# Regensensor.net
KiCad netlist of a schematic drawn in EAGLE
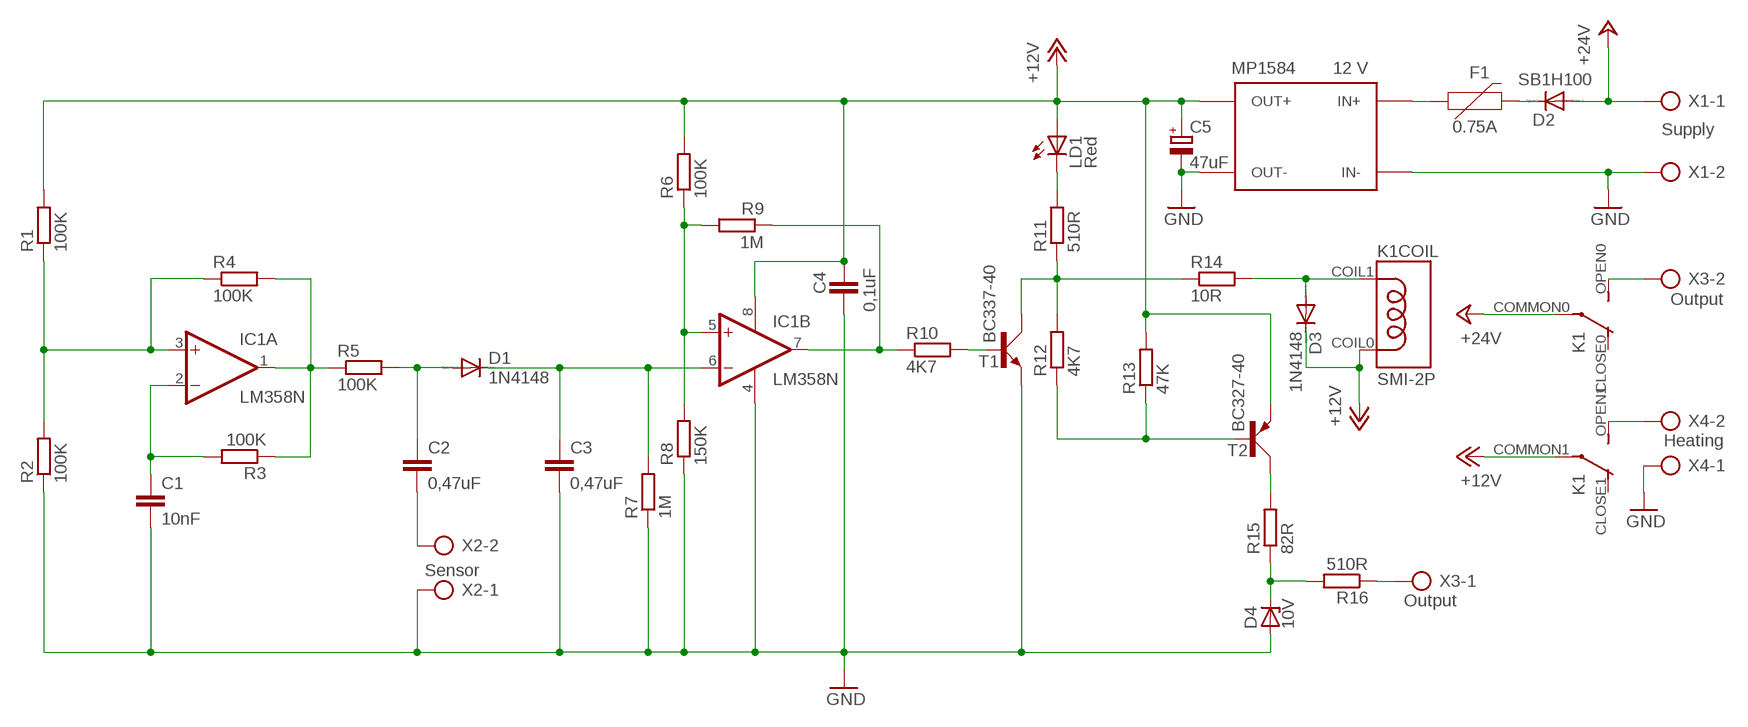
[diagram p0: schematic, sheet 1]

(export (version "E")
  (design (tool "Eeschema 10.0.6"))
  (components
    (comp (ref "C1")
      (value "10nF")
      (footprint "eagle-import:C050-055X075")
      (libsource (lib "eagle-import") (part "C-EU050-055X075"))
    )
    (comp (ref "C2")
      (value "0,47uF")
      (footprint "eagle-import:C050-035X075")
      (libsource (lib "eagle-import") (part "C-EU050-035X075"))
    )
    (comp (ref "C3")
      (value "0,47uF")
      (footprint "eagle-import:C050-035X075")
      (libsource (lib "eagle-import") (part "C-EU050-035X075"))
    )
    (comp (ref "C4")
      (value "0,1uF")
      (footprint "eagle-import:C025-030X050")
      (libsource (lib "eagle-import") (part "C-EU025-030X050"))
    )
    (comp (ref "C5")
      (value "47uF")
      (footprint "eagle-import:E2,5-7")
      (libsource (lib "eagle-import") (part "CPOL-EUE2.5-7"))
    )
    (comp (ref "D1")
      (value "1N4148")
      (footprint "eagle-import:DO35-2V")
      (libsource (lib "eagle-import") (part "1N4148DO35-2V"))
    )
    (comp (ref "D2")
      (value "SB1H100")
      (footprint "eagle-import:DO41-7.6")
      (libsource (lib "eagle-import") (part "DIODE-DO41-7.6"))
    )
    (comp (ref "D3")
      (value "1N4148")
      (footprint "eagle-import:DO35-7")
      (libsource (lib "eagle-import") (part "1N4148DO35-7"))
    )
    (comp (ref "D4")
      (value "10V")
      (footprint "eagle-import:ZDIO-2.5")
      (libsource (lib "eagle-import") (part "ZENER-DIODEZD-2.5"))
    )
    (comp (ref "F1")
      (value "0.75A")
      (footprint "eagle-import:RGEF250")
      (libsource (lib "eagle-import") (part "PPTCRGEF250"))
    )
    (comp (ref "IC1")
      (value "LM358N")
      (footprint "eagle-import:DIL08")
      (libsource (lib "eagle-import") (part "LM358N"))
    )
    (comp (ref "K1")
      (value "SMI-2P")
      (footprint "eagle-import:SMI")
      (libsource (lib "eagle-import") (part "SMI-2P"))
    )
    (comp (ref "LD1")
      (value "Red")
      (footprint "eagle-import:LED5MM")
      (libsource (lib "eagle-import") (part "LED5MM"))
    )
    (comp (ref "MP1584")
      (value "12 V")
      (footprint "eagle-import:MP1584")
      (libsource (lib "eagle-import") (part "DC-DC-STEP-DOWNMP1584"))
    )
    (comp (ref "R1")
      (value "100K")
      (footprint "eagle-import:0204V")
      (libsource (lib "eagle-import") (part "R-EU_0204/2V"))
    )
    (comp (ref "R2")
      (value "100K")
      (footprint "eagle-import:0204V")
      (libsource (lib "eagle-import") (part "R-EU_0204/2V"))
    )
    (comp (ref "R3")
      (value "100K")
      (footprint "eagle-import:0204V")
      (libsource (lib "eagle-import") (part "R-EU_0204/2V"))
    )
    (comp (ref "R4")
      (value "100K")
      (footprint "eagle-import:0204_5")
      (libsource (lib "eagle-import") (part "R-EU_0204/5"))
    )
    (comp (ref "R5")
      (value "100K")
      (footprint "eagle-import:0204V")
      (libsource (lib "eagle-import") (part "R-EU_0204/2V"))
    )
    (comp (ref "R6")
      (value "100K")
      (footprint "eagle-import:0204_5")
      (libsource (lib "eagle-import") (part "R-EU_0204/5"))
    )
    (comp (ref "R7")
      (value "1M")
      (footprint "eagle-import:0204V")
      (libsource (lib "eagle-import") (part "R-EU_0204/2V"))
    )
    (comp (ref "R8")
      (value "150K")
      (footprint "eagle-import:0204_5")
      (libsource (lib "eagle-import") (part "R-EU_0204/5"))
    )
    (comp (ref "R9")
      (value "1M")
      (footprint "eagle-import:0204_5")
      (libsource (lib "eagle-import") (part "R-EU_0204/5"))
    )
    (comp (ref "R10")
      (value "4K7")
      (footprint "eagle-import:0204_5")
      (libsource (lib "eagle-import") (part "R-EU_0204/5"))
    )
    (comp (ref "R11")
      (value "510R")
      (footprint "eagle-import:0204V")
      (libsource (lib "eagle-import") (part "R-EU_0204/2V"))
    )
    (comp (ref "R12")
      (value "4K7")
      (footprint "eagle-import:0204V")
      (libsource (lib "eagle-import") (part "R-EU_0204/2V"))
    )
    (comp (ref "R13")
      (value "47K")
      (footprint "eagle-import:0204V")
      (libsource (lib "eagle-import") (part "R-EU_0204/2V"))
    )
    (comp (ref "R14")
      (value "10R")
      (footprint "eagle-import:0204V")
      (libsource (lib "eagle-import") (part "R-EU_0204/2V"))
    )
    (comp (ref "R15")
      (value "82R")
      (footprint "eagle-import:0204V")
      (libsource (lib "eagle-import") (part "R-EU_0204/2V"))
    )
    (comp (ref "R16")
      (value "510R")
      (footprint "eagle-import:0204V")
      (libsource (lib "eagle-import") (part "R-EU_0204/2V"))
    )
    (comp (ref "T1")
      (value "BC337-40")
      (footprint "eagle-import:TO92-LINE")
      (libsource (lib "eagle-import") (part "BC337LINE"))
    )
    (comp (ref "T2")
      (value "BC327-40")
      (footprint "eagle-import:TO92-LINE")
      (libsource (lib "eagle-import") (part "BC327LINE"))
    )
    (comp (ref "X1")
      (value "Supply")
      (footprint "eagle-import:MKDSB-3_2-2")
      (libsource (lib "eagle-import") (part "MKDS-3/25,08"))
    )
    (comp (ref "X2")
      (value "Sensor")
      (footprint "eagle-import:MKDSB-3_2-2")
      (libsource (lib "eagle-import") (part "MKDS-3/25,08"))
    )
    (comp (ref "X3")
      (value "Output")
      (footprint "eagle-import:MKDSB-3_2-2")
      (libsource (lib "eagle-import") (part "MKDS-3/25,08"))
    )
    (comp (ref "X4")
      (value "Heating")
      (footprint "eagle-import:MKDSB-3_2-2")
      (libsource (lib "eagle-import") (part "MKDS-3/25,08"))
    )
  )
  (nets
    (net (code "1") (name "+12V") (class "Default")
      (node (ref "C4") (pin "1") (pinfunction "1_1") (pintype "passive"))
      (node (ref "C5") (pin "+") (pinfunction "+_+") (pintype "passive"))
      (node (ref "D3") (pin "C") (pinfunction "C_C") (pintype "passive"))
      (node (ref "IC1") (pin "8") (pinfunction "V+_8") (pintype "power_in"))
      (node (ref "K1") (pin "COIL0") (pinfunction "0_COIL0") (pintype "passive"))
      (node (ref "K1") (pin "COMMON1") (pinfunction "COMMON_COMMON1") (pintype "passive"))
      (node (ref "LD1") (pin "A") (pinfunction "A_A") (pintype "passive"))
      (node (ref "MP1584") (pin "OUT+0") (pinfunction "OUT+_OUT+0") (pintype "power_in"))
      (node (ref "MP1584") (pin "OUT+1") (pinfunction "OUT+_OUT+1") (pintype "power_in"))
      (node (ref "R1") (pin "2") (pinfunction "2_2") (pintype "passive"))
      (node (ref "R13") (pin "2") (pinfunction "2_2") (pintype "passive"))
      (node (ref "R6") (pin "2") (pinfunction "2_2") (pintype "passive"))
      (node (ref "T2") (pin "1") (pinfunction "E_1") (pintype "passive"))
    )
    (net (code "2") (name "+24V") (class "Default")
      (node (ref "D2") (pin "A") (pinfunction "A_A") (pintype "passive"))
      (node (ref "K1") (pin "COMMON0") (pinfunction "COMMON_COMMON0") (pintype "passive"))
      (node (ref "X1") (pin "1") (pinfunction "KL_1") (pintype "passive"))
    )
    (net (code "3") (name "GND") (class "Default")
      (node (ref "C1") (pin "2") (pinfunction "2_2") (pintype "passive"))
      (node (ref "C3") (pin "2") (pinfunction "2_2") (pintype "passive"))
      (node (ref "C4") (pin "2") (pinfunction "2_2") (pintype "passive"))
      (node (ref "C5") (pin "-") (pinfunction "-_-") (pintype "passive"))
      (node (ref "D4") (pin "A") (pinfunction "A_A") (pintype "passive"))
      (node (ref "IC1") (pin "4") (pinfunction "V-_4") (pintype "power_in"))
      (node (ref "MP1584") (pin "IN-0") (pinfunction "IN-_IN-0") (pintype "power_in"))
      (node (ref "MP1584") (pin "IN-1") (pinfunction "IN-_IN-1") (pintype "power_in"))
      (node (ref "MP1584") (pin "OUT-0") (pinfunction "OUT-_OUT-0") (pintype "power_in"))
      (node (ref "MP1584") (pin "OUT-1") (pinfunction "OUT-_OUT-1") (pintype "power_in"))
      (node (ref "R2") (pin "1") (pinfunction "1_1") (pintype "passive"))
      (node (ref "R7") (pin "1") (pinfunction "1_1") (pintype "passive"))
      (node (ref "R8") (pin "1") (pinfunction "1_1") (pintype "passive"))
      (node (ref "T1") (pin "1") (pinfunction "E_1") (pintype "passive"))
      (node (ref "X1") (pin "2") (pinfunction "KL_2") (pintype "passive"))
      (node (ref "X2") (pin "1") (pinfunction "KL_1") (pintype "passive"))
      (node (ref "X4") (pin "1") (pinfunction "KL_1") (pintype "passive"))
    )
    (net (code "4") (name "Net-(C2-Pad1)") (class "Default")
      (node (ref "C2") (pin "1") (pinfunction "1_1") (pintype "passive"))
      (node (ref "D1") (pin "A") (pinfunction "A_A") (pintype "passive"))
      (node (ref "R5") (pin "2") (pinfunction "2_2") (pintype "passive"))
    )
    (net (code "5") (name "Net-(D4-PadC)") (class "Default")
      (node (ref "D4") (pin "C") (pinfunction "C_C") (pintype "passive"))
      (node (ref "R15") (pin "1") (pinfunction "1_1") (pintype "passive"))
      (node (ref "R16") (pin "2") (pinfunction "2_2") (pintype "passive"))
    )
    (net (code "6") (name "Net-(F1-1)") (class "Default")
      (node (ref "F1") (pin "P$1") (pinfunction "1_P$1") (pintype "bidirectional"))
      (node (ref "MP1584") (pin "IN+0") (pinfunction "IN+_IN+0") (pintype "power_in"))
      (node (ref "MP1584") (pin "IN+1") (pinfunction "IN+_IN+1") (pintype "power_in"))
    )
    (net (code "7") (name "Net-(F1-2)") (class "Default")
      (node (ref "D2") (pin "C") (pinfunction "C_C") (pintype "passive"))
      (node (ref "F1") (pin "P$2") (pinfunction "2_P$2") (pintype "bidirectional"))
    )
    (net (code "8") (name "Net-(IC1A-+IN)") (class "Default")
      (node (ref "IC1") (pin "3") (pinfunction "+IN_3") (pintype "input"))
      (node (ref "R1") (pin "1") (pinfunction "1_1") (pintype "passive"))
      (node (ref "R2") (pin "2") (pinfunction "2_2") (pintype "passive"))
      (node (ref "R4") (pin "1") (pinfunction "1_1") (pintype "passive"))
    )
    (net (code "9") (name "Net-(IC1A--IN)") (class "Default")
      (node (ref "C1") (pin "1") (pinfunction "1_1") (pintype "passive"))
      (node (ref "IC1") (pin "2") (pinfunction "-IN_2") (pintype "input"))
      (node (ref "R3") (pin "2") (pinfunction "2_2") (pintype "passive"))
    )
    (net (code "10") (name "Net-(IC1A-OUT)") (class "Default")
      (node (ref "IC1") (pin "1") (pinfunction "OUT_1") (pintype "output"))
      (node (ref "R3") (pin "1") (pinfunction "1_1") (pintype "passive"))
      (node (ref "R4") (pin "2") (pinfunction "2_2") (pintype "passive"))
      (node (ref "R5") (pin "1") (pinfunction "1_1") (pintype "passive"))
    )
    (net (code "11") (name "Net-(IC1B-+IN)") (class "Default")
      (node (ref "IC1") (pin "5") (pinfunction "+IN_5") (pintype "input"))
      (node (ref "R6") (pin "1") (pinfunction "1_1") (pintype "passive"))
      (node (ref "R8") (pin "2") (pinfunction "2_2") (pintype "passive"))
      (node (ref "R9") (pin "2") (pinfunction "2_2") (pintype "passive"))
    )
    (net (code "12") (name "Net-(IC1B--IN)") (class "Default")
      (node (ref "C3") (pin "1") (pinfunction "1_1") (pintype "passive"))
      (node (ref "D1") (pin "C") (pinfunction "C_C") (pintype "passive"))
      (node (ref "IC1") (pin "6") (pinfunction "-IN_6") (pintype "input"))
      (node (ref "R7") (pin "2") (pinfunction "2_2") (pintype "passive"))
    )
    (net (code "13") (name "Net-(IC1B-OUT)") (class "Default")
      (node (ref "IC1") (pin "7") (pinfunction "OUT_7") (pintype "output"))
      (node (ref "R10") (pin "1") (pinfunction "1_1") (pintype "passive"))
      (node (ref "R9") (pin "1") (pinfunction "1_1") (pintype "passive"))
    )
    (net (code "14") (name "Net-(K1A-1)") (class "Default")
      (node (ref "D3") (pin "A") (pinfunction "A_A") (pintype "passive"))
      (node (ref "K1") (pin "COIL1") (pinfunction "1_COIL1") (pintype "passive"))
      (node (ref "R14") (pin "2") (pinfunction "2_2") (pintype "passive"))
    )
    (net (code "15") (name "Net-(K1B-OPEN)") (class "Default")
      (node (ref "K1") (pin "OPEN0") (pinfunction "OPEN_OPEN0") (pintype "passive"))
      (node (ref "X3") (pin "2") (pinfunction "KL_2") (pintype "passive"))
    )
    (net (code "16") (name "Net-(K1C-OPEN)") (class "Default")
      (node (ref "K1") (pin "OPEN1") (pinfunction "OPEN_OPEN1") (pintype "passive"))
      (node (ref "X4") (pin "2") (pinfunction "KL_2") (pintype "passive"))
    )
    (net (code "17") (name "Net-(LD1-C)") (class "Default")
      (node (ref "LD1") (pin "K") (pinfunction "C_K") (pintype "passive"))
      (node (ref "R11") (pin "2") (pinfunction "2_2") (pintype "passive"))
    )
    (net (code "18") (name "Net-(T1-B)") (class "Default")
      (node (ref "R10") (pin "2") (pinfunction "2_2") (pintype "passive"))
      (node (ref "T1") (pin "2") (pinfunction "B_2") (pintype "passive"))
    )
    (net (code "19") (name "Net-(T1-C)") (class "Default")
      (node (ref "R11") (pin "1") (pinfunction "1_1") (pintype "passive"))
      (node (ref "R12") (pin "2") (pinfunction "2_2") (pintype "passive"))
      (node (ref "R14") (pin "1") (pinfunction "1_1") (pintype "passive"))
      (node (ref "T1") (pin "3") (pinfunction "C_3") (pintype "passive"))
    )
    (net (code "20") (name "Net-(T2-B)") (class "Default")
      (node (ref "R12") (pin "1") (pinfunction "1_1") (pintype "passive"))
      (node (ref "R13") (pin "1") (pinfunction "1_1") (pintype "passive"))
      (node (ref "T2") (pin "2") (pinfunction "B_2") (pintype "passive"))
    )
    (net (code "21") (name "Net-(T2-C)") (class "Default")
      (node (ref "R15") (pin "2") (pinfunction "2_2") (pintype "passive"))
      (node (ref "T2") (pin "3") (pinfunction "C_3") (pintype "passive"))
    )
    (net (code "22") (name "Net-(X2B-KL)") (class "Default")
      (node (ref "C2") (pin "2") (pinfunction "2_2") (pintype "passive"))
      (node (ref "X2") (pin "2") (pinfunction "KL_2") (pintype "passive"))
    )
    (net (code "23") (name "Net-(X3A-KL)") (class "Default")
      (node (ref "R16") (pin "1") (pinfunction "1_1") (pintype "passive"))
      (node (ref "X3") (pin "1") (pinfunction "KL_1") (pintype "passive"))
    )
    (net (code "24") (name "unconnected-(K1B-CLOSE-PadCLOSE0)") (class "Default")
      (node (ref "K1") (pin "CLOSE0") (pinfunction "CLOSE_CLOSE0") (pintype "passive"))
    )
    (net (code "25") (name "unconnected-(K1C-CLOSE-PadCLOSE1)") (class "Default")
      (node (ref "K1") (pin "CLOSE1") (pinfunction "CLOSE_CLOSE1") (pintype "passive"))
    )
  )
)
